# reference_voltage.net
KiCad netlist of a schematic drawn in Altium Designer
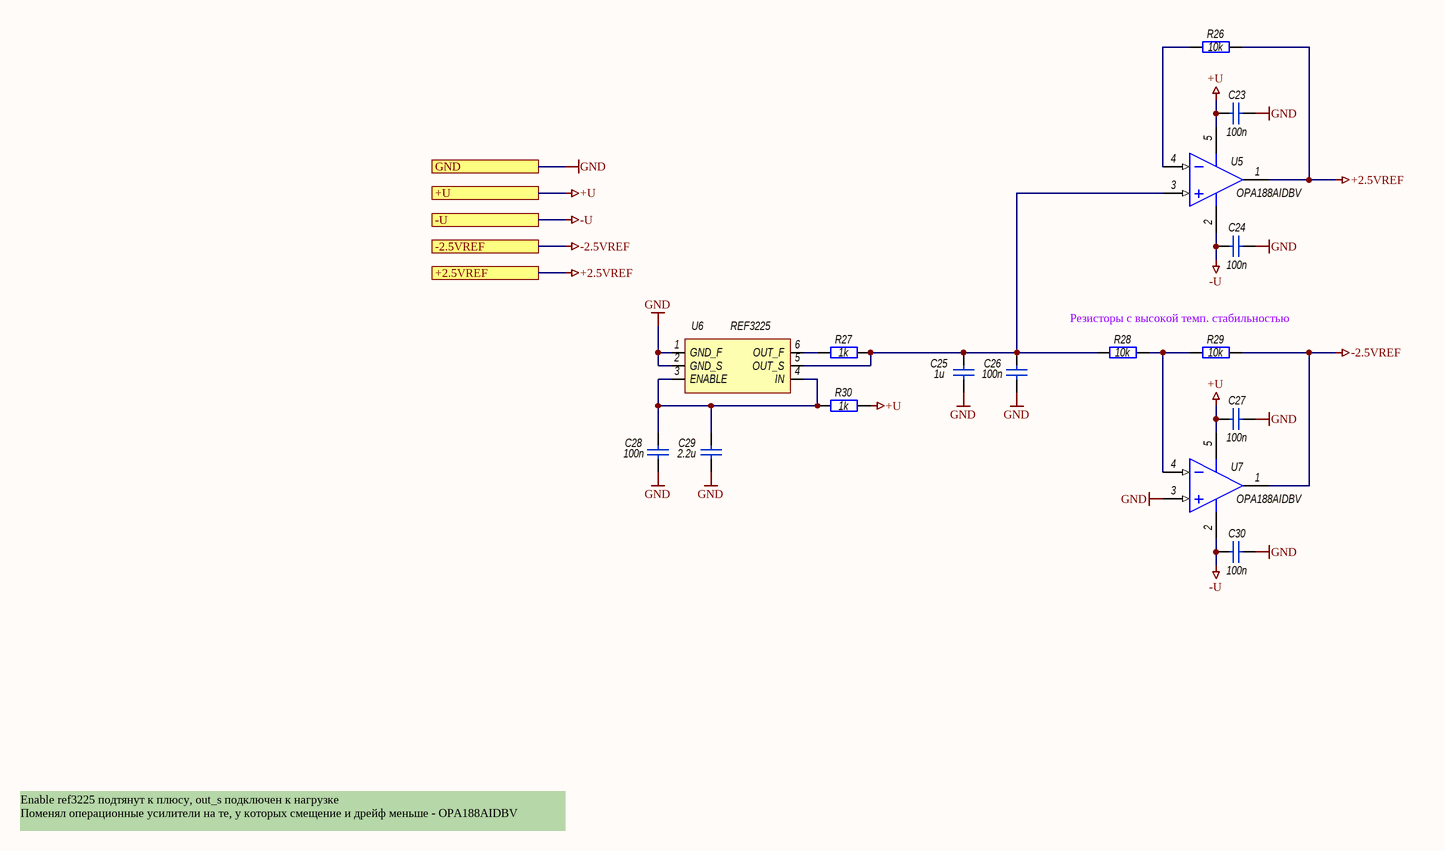
[diagram p0: reference_voltage.SchDoc]

(export (version "E")
  (design (tool "Eeschema 10.0.6"))
  (components
    (comp (ref "C23")
      (value "100n")
      (footprint "CAP_0603")
      (description "Конденсатор")
      (libsource (lib "SCH_LIB") (part "Capacitor"))
    )
    (comp (ref "C24")
      (value "100n")
      (footprint "CAP_0603")
      (description "Конденсатор")
      (libsource (lib "SCH_LIB") (part "Capacitor"))
    )
    (comp (ref "C25")
      (value "1u")
      (footprint "CAP_0603")
      (description "Конденсатор")
      (libsource (lib "SCH_LIB") (part "Capacitor"))
    )
    (comp (ref "C26")
      (value "100n")
      (footprint "CAP_0603")
      (description "Конденсатор")
      (libsource (lib "SCH_LIB") (part "Capacitor"))
    )
    (comp (ref "C27")
      (value "100n")
      (footprint "CAP_0603")
      (description "Конденсатор")
      (libsource (lib "SCH_LIB") (part "Capacitor"))
    )
    (comp (ref "C28")
      (value "100n")
      (footprint "CAP_0603")
      (description "Конденсатор")
      (libsource (lib "SCH_LIB") (part "Capacitor"))
    )
    (comp (ref "C29")
      (value "2.2u")
      (footprint "CAP_0603")
      (description "Конденсатор")
      (libsource (lib "SCH_LIB") (part "Capacitor"))
    )
    (comp (ref "C30")
      (value "100n")
      (footprint "CAP_0603")
      (description "Конденсатор")
      (libsource (lib "SCH_LIB") (part "Capacitor"))
    )
    (comp (ref "R26")
      (value "10k")
      (footprint "RES_0603")
      (description "Резистор")
      (libsource (lib "SCH_LIB") (part "Resisitor"))
    )
    (comp (ref "R27")
      (value "1k")
      (footprint "RES_0603")
      (description "Резистор")
      (libsource (lib "SCH_LIB") (part "Resisitor"))
    )
    (comp (ref "R28")
      (value "10k")
      (footprint "RES_0603")
      (description "Резистор")
      (libsource (lib "SCH_LIB") (part "Resisitor"))
    )
    (comp (ref "R29")
      (value "10k")
      (footprint "RES_0603")
      (description "Резистор")
      (libsource (lib "SCH_LIB") (part "Resisitor"))
    )
    (comp (ref "R30")
      (value "1k")
      (footprint "RES_0603")
      (description "Резистор")
      (libsource (lib "SCH_LIB") (part "Resisitor"))
    )
    (comp (ref "U5")
      (value "OPA188AIDBV")
      (footprint "sot235")
      (description "Операционный усилитель")
      (libsource (lib "SCH_LIB") (part "OPAMP SOT235"))
    )
    (comp (ref "U6")
      (value "REF3225")
      (footprint "PCB_LIB:SOT236")
      (description "Источник опорного напряжения")
      (libsource (lib "SCH_LIB") (part "REF32xx"))
    )
    (comp (ref "U7")
      (value "OPA188AIDBV")
      (footprint "sot235")
      (description "Операционный усилитель")
      (libsource (lib "SCH_LIB") (part "OPAMP SOT235"))
    )
  )
  (nets
    (net (code "1") (name "+2.5VREF") (class "Default")
      (node (ref "R26") (pin "2") (pinfunction "2_2") (pintype "passive"))
      (node (ref "U5") (pin "1") (pinfunction "OUT_1") (pintype "open_collector"))
    )
    (net (code "2") (name "+U") (class "Default")
      (node (ref "C23") (pin "1") (pinfunction "1_1") (pintype "passive"))
      (node (ref "C27") (pin "1") (pinfunction "1_1") (pintype "passive"))
      (node (ref "R30") (pin "2") (pinfunction "2_2") (pintype "passive"))
      (node (ref "U5") (pin "5") (pinfunction "V+_5") (pintype "power_in"))
      (node (ref "U7") (pin "5") (pinfunction "V+_5") (pintype "power_in"))
    )
    (net (code "3") (name "-2.5VREF") (class "Default")
      (node (ref "R29") (pin "2") (pinfunction "2_2") (pintype "passive"))
      (node (ref "U7") (pin "1") (pinfunction "OUT_1") (pintype "open_collector"))
    )
    (net (code "4") (name "-U") (class "Default")
      (node (ref "C24") (pin "1") (pinfunction "1_1") (pintype "passive"))
      (node (ref "C30") (pin "1") (pinfunction "1_1") (pintype "passive"))
      (node (ref "U5") (pin "2") (pinfunction "V-_2") (pintype "power_in"))
      (node (ref "U7") (pin "2") (pinfunction "V-_2") (pintype "power_in"))
    )
    (net (code "5") (name "GND") (class "Default")
      (node (ref "C23") (pin "2") (pinfunction "2_2") (pintype "passive"))
      (node (ref "C24") (pin "2") (pinfunction "2_2") (pintype "passive"))
      (node (ref "C25") (pin "1") (pinfunction "1_1") (pintype "passive"))
      (node (ref "C26") (pin "1") (pinfunction "1_1") (pintype "passive"))
      (node (ref "C27") (pin "2") (pinfunction "2_2") (pintype "passive"))
      (node (ref "C28") (pin "1") (pinfunction "1_1") (pintype "passive"))
      (node (ref "C29") (pin "1") (pinfunction "1_1") (pintype "passive"))
      (node (ref "C30") (pin "2") (pinfunction "2_2") (pintype "passive"))
      (node (ref "U6") (pin "1") (pinfunction "GND_F_1") (pintype "passive"))
      (node (ref "U6") (pin "2") (pinfunction "GND_S_2") (pintype "passive"))
      (node (ref "U7") (pin "3") (pinfunction "IN+_3") (pintype "input"))
    )
    (net (code "6") (name "Net-(U5-IN+)") (class "Default")
      (node (ref "C25") (pin "2") (pinfunction "2_2") (pintype "passive"))
      (node (ref "C26") (pin "2") (pinfunction "2_2") (pintype "passive"))
      (node (ref "R27") (pin "2") (pinfunction "2_2") (pintype "passive"))
      (node (ref "R28") (pin "1") (pinfunction "1_1") (pintype "passive"))
      (node (ref "U5") (pin "3") (pinfunction "IN+_3") (pintype "input"))
      (node (ref "U6") (pin "5") (pinfunction "OUT_S_5") (pintype "passive"))
    )
    (net (code "7") (name "Net-(U5-IN-)") (class "Default")
      (node (ref "R26") (pin "1") (pinfunction "1_1") (pintype "passive"))
      (node (ref "U5") (pin "4") (pinfunction "IN-_4") (pintype "input"))
    )
    (net (code "8") (name "Net-(U6-ENABLE)") (class "Default")
      (node (ref "C28") (pin "2") (pinfunction "2_2") (pintype "passive"))
      (node (ref "C29") (pin "2") (pinfunction "2_2") (pintype "passive"))
      (node (ref "R30") (pin "1") (pinfunction "1_1") (pintype "passive"))
      (node (ref "U6") (pin "3") (pinfunction "ENABLE_3") (pintype "passive"))
      (node (ref "U6") (pin "4") (pinfunction "IN_4") (pintype "passive"))
    )
    (net (code "9") (name "Net-(U6-OUT_F)") (class "Default")
      (node (ref "R27") (pin "1") (pinfunction "1_1") (pintype "passive"))
      (node (ref "U6") (pin "6") (pinfunction "OUT_F_6") (pintype "passive"))
    )
    (net (code "10") (name "Net-(U7-IN-)") (class "Default")
      (node (ref "R28") (pin "2") (pinfunction "2_2") (pintype "passive"))
      (node (ref "R29") (pin "1") (pinfunction "1_1") (pintype "passive"))
      (node (ref "U7") (pin "4") (pinfunction "IN-_4") (pintype "input"))
    )
  )
)
